# dual_5v.net
KiCad netlist of a schematic drawn in EAGLE
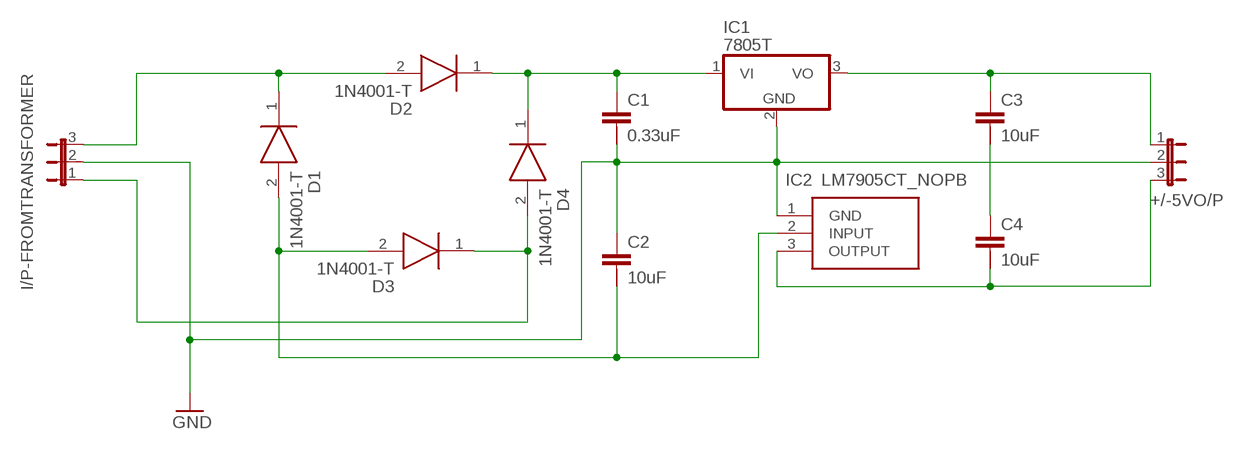
[diagram p0: schematic, sheet 1]

(export (version "E")
  (design (tool "Eeschema 10.0.6"))
  (components
    (comp (ref "+/-5VO/P")
      (value "JP2E")
      (footprint "eagle-import:JP2")
      (libsource (lib "eagle-import") (part "JP2E"))
    )
    (comp (ref "C1")
      (value "0.33uF")
      (footprint "eagle-import:C2.5_5-2")
      (libsource (lib "eagle-import") (part "C-2.5-5/2"))
    )
    (comp (ref "C2")
      (value "10uF")
      (footprint "eagle-import:C2.5_5-2")
      (libsource (lib "eagle-import") (part "C-2.5-5/2"))
    )
    (comp (ref "C3")
      (value "10uF")
      (footprint "eagle-import:C2.5_5-2")
      (libsource (lib "eagle-import") (part "C-2.5-5/2"))
    )
    (comp (ref "C4")
      (value "10uF")
      (footprint "eagle-import:C2.5_5-2")
      (libsource (lib "eagle-import") (part "C-2.5-5/2"))
    )
    (comp (ref "D1")
      (value "1N4001-T")
      (footprint "eagle-import:DIOAD1408W86L464D236")
      (fields (field (name "MOUSER_PART_NUMBER") "621-1N4001"))
      (libsource (lib "eagle-import") (part "1N4001-T"))
    )
    (comp (ref "D2")
      (value "1N4001-T")
      (footprint "eagle-import:DIOAD1408W86L464D236")
      (fields (field (name "MOUSER_PART_NUMBER") "621-1N4001"))
      (libsource (lib "eagle-import") (part "1N4001-T"))
    )
    (comp (ref "D3")
      (value "1N4001-T")
      (footprint "eagle-import:DIOAD1408W86L464D236")
      (fields (field (name "MOUSER_PART_NUMBER") "621-1N4001"))
      (libsource (lib "eagle-import") (part "1N4001-T"))
    )
    (comp (ref "D4")
      (value "1N4001-T")
      (footprint "eagle-import:DIOAD1408W86L464D236")
      (fields (field (name "MOUSER_PART_NUMBER") "621-1N4001"))
      (libsource (lib "eagle-import") (part "1N4001-T"))
    )
    (comp (ref "I/P-FROMTRANSFORMER")
      (value "JP2E")
      (footprint "eagle-import:JP2")
      (libsource (lib "eagle-import") (part "JP2E"))
    )
    (comp (ref "IC1")
      (value "7805T")
      (footprint "eagle-import:TO220H")
      (libsource (lib "eagle-import") (part "78T05"))
    )
    (comp (ref "IC2")
      (value "LM7905CT_NOPB")
      (footprint "eagle-import:TO254P470X1028X1955-3P")
      (fields
        (field (name "ARROW_PART_NUMBER") "LM7905CT/NOPB")
        (field (name "MOUSER_PART_NUMBER") "926-LM7905CT/NOPB")
      )
      (libsource (lib "eagle-import") (part "LM7905CT_NOPB"))
    )
  )
  (nets
    (net (code "1") (name "GND") (class "Default")
      (node (ref "+/-5VO/P") (pin "2") (pinfunction "2_2") (pintype "passive"))
      (node (ref "C1") (pin "2") (pinfunction "2_2") (pintype "passive"))
      (node (ref "C2") (pin "1") (pinfunction "1_1") (pintype "passive"))
      (node (ref "I/P-FROMTRANSFORMER") (pin "2") (pinfunction "2_2") (pintype "passive"))
      (node (ref "IC1") (pin "2") (pinfunction "GND_2") (pintype "passive"))
      (node (ref "IC2") (pin "1") (pinfunction "GND_1") (pintype "bidirectional"))
    )
    (net (code "2") (name "Net-(C3-Pad2)") (class "Default")
      (node (ref "C3") (pin "2") (pinfunction "2_2") (pintype "passive"))
      (node (ref "C4") (pin "1") (pinfunction "1_1") (pintype "passive"))
    )
    (net (code "3") (name "Net-(D1-A)") (class "Default")
      (node (ref "C2") (pin "2") (pinfunction "2_2") (pintype "passive"))
      (node (ref "D1") (pin "2") (pinfunction "A_2") (pintype "bidirectional"))
      (node (ref "D3") (pin "2") (pinfunction "A_2") (pintype "bidirectional"))
      (node (ref "IC2") (pin "2") (pinfunction "INPUT_2") (pintype "bidirectional"))
    )
    (net (code "4") (name "Net-(D1-K)") (class "Default")
      (node (ref "D1") (pin "1") (pinfunction "K_1") (pintype "bidirectional"))
      (node (ref "D2") (pin "2") (pinfunction "A_2") (pintype "bidirectional"))
      (node (ref "I/P-FROMTRANSFORMER") (pin "3") (pinfunction "3_3") (pintype "passive"))
    )
    (net (code "5") (name "Net-(D2-K)") (class "Default")
      (node (ref "C1") (pin "1") (pinfunction "1_1") (pintype "passive"))
      (node (ref "D2") (pin "1") (pinfunction "K_1") (pintype "bidirectional"))
      (node (ref "D4") (pin "1") (pinfunction "K_1") (pintype "bidirectional"))
      (node (ref "IC1") (pin "1") (pinfunction "VI_1") (pintype "input"))
    )
    (net (code "6") (name "Net-(D3-K)") (class "Default")
      (node (ref "D3") (pin "1") (pinfunction "K_1") (pintype "bidirectional"))
      (node (ref "D4") (pin "2") (pinfunction "A_2") (pintype "bidirectional"))
      (node (ref "I/P-FROMTRANSFORMER") (pin "1") (pinfunction "1_1") (pintype "passive"))
    )
    (net (code "7") (name "Net-(IC1-VO)") (class "Default")
      (node (ref "+/-5VO/P") (pin "1") (pinfunction "1_1") (pintype "passive"))
      (node (ref "C3") (pin "1") (pinfunction "1_1") (pintype "passive"))
      (node (ref "IC1") (pin "3") (pinfunction "VO_3") (pintype "passive"))
    )
    (net (code "8") (name "Net-(IC2-OUTPUT)") (class "Default")
      (node (ref "+/-5VO/P") (pin "3") (pinfunction "3_3") (pintype "passive"))
      (node (ref "C4") (pin "2") (pinfunction "2_2") (pintype "passive"))
      (node (ref "IC2") (pin "3") (pinfunction "OUTPUT_3") (pintype "bidirectional"))
    )
    (net (code "9") (name "unconnected-(C1-Pad3)") (class "Default")
      (node (ref "C1") (pin "3") (pinfunction "3_3") (pintype "passive"))
    )
    (net (code "10") (name "unconnected-(C2-Pad3)") (class "Default")
      (node (ref "C2") (pin "3") (pinfunction "3_3") (pintype "passive"))
    )
    (net (code "11") (name "unconnected-(C3-Pad3)") (class "Default")
      (node (ref "C3") (pin "3") (pinfunction "3_3") (pintype "passive"))
    )
    (net (code "12") (name "unconnected-(C4-Pad3)") (class "Default")
      (node (ref "C4") (pin "3") (pinfunction "3_3") (pintype "passive"))
    )
  )
)
